# mikromedia_shield.net
KiCad netlist of a schematic drawn in EAGLE
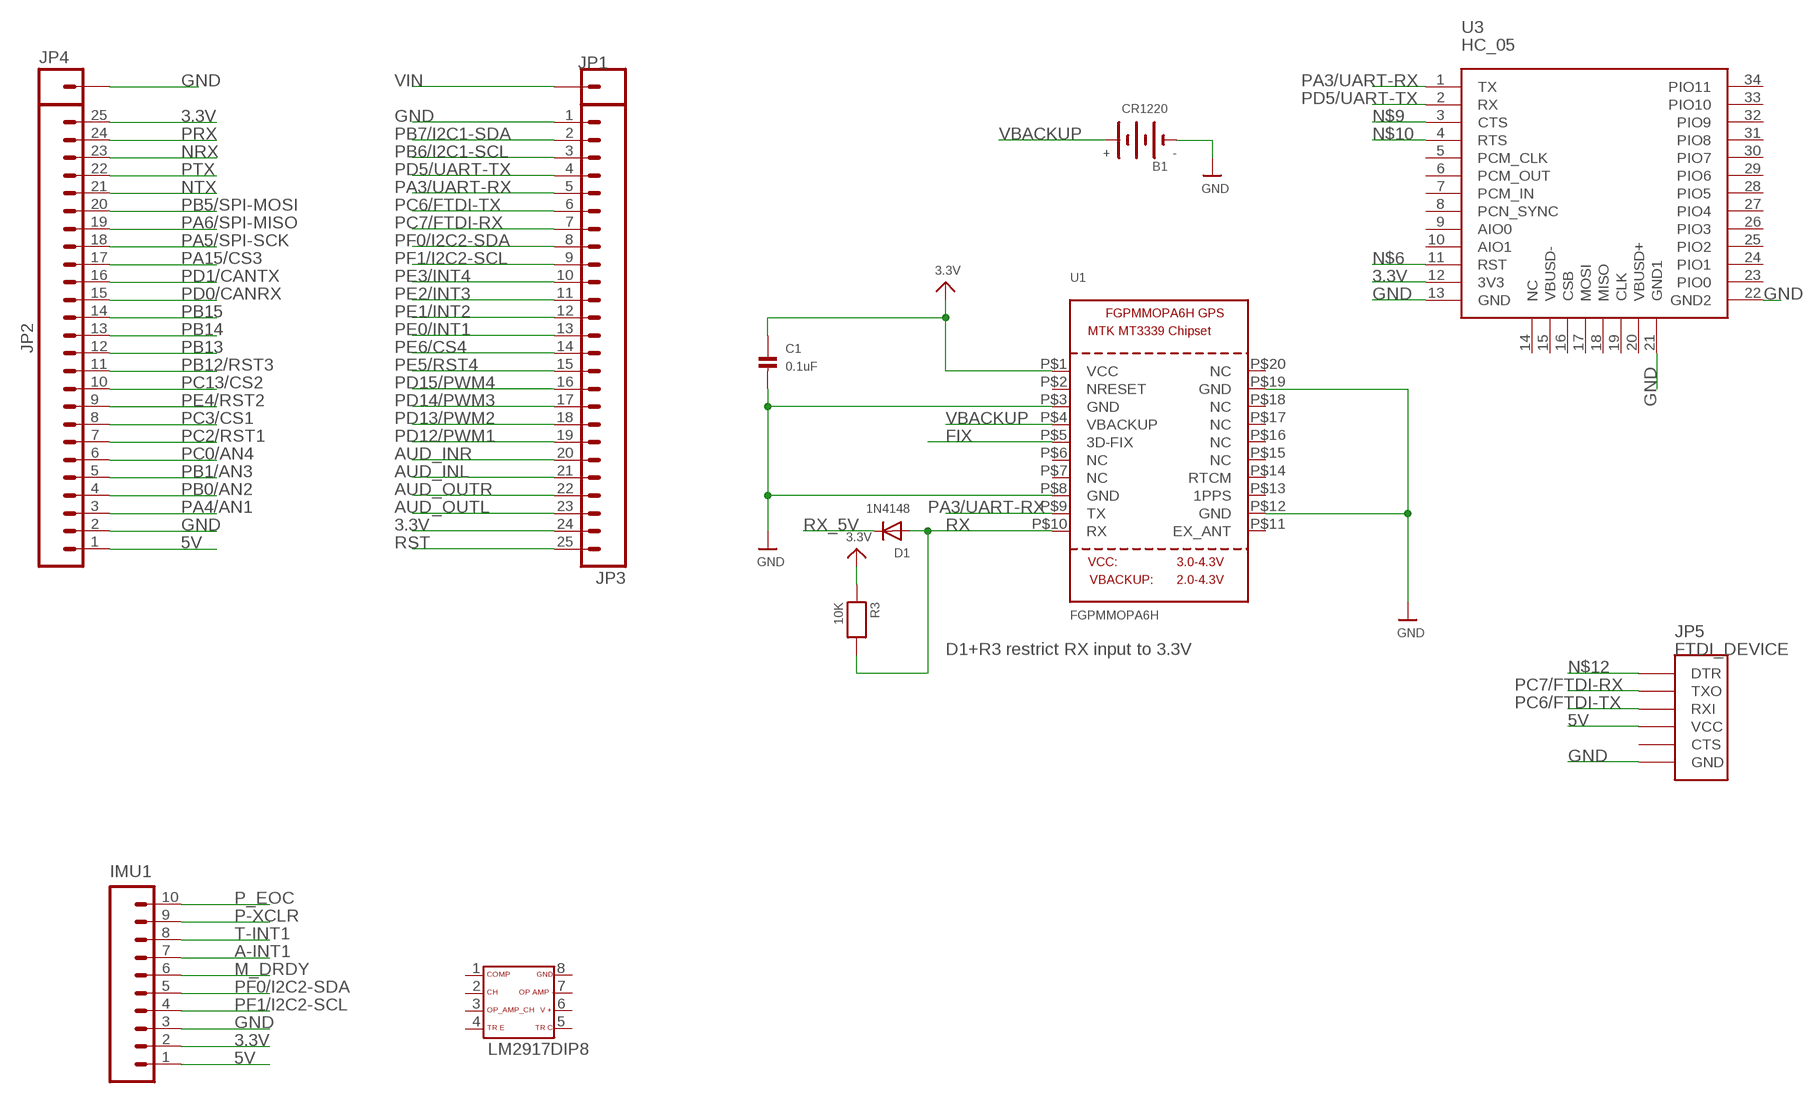
[diagram p0: schematic, sheet 1]

(export (version "E")
  (design (tool "Eeschema 10.0.6"))
  (components
    (comp (ref "B1")
      (value "CR1220")
      (footprint "eagle-import:CR1220")
      (libsource (lib "eagle-import") (part "BATTERYCR1220_SMT"))
    )
    (comp (ref "C1")
      (value "0.1uF")
      (footprint "eagle-import:0805")
      (libsource (lib "eagle-import") (part "CAP_CERAMIC0805"))
    )
    (comp (ref "D1")
      (value "1N4148")
      (footprint "eagle-import:SOD-323F")
      (libsource (lib "eagle-import") (part "DIODESOD-323F"))
    )
    (comp (ref "IC1")
      (value "LM2917DIP8")
      (footprint "eagle-import:LM2917_DIP8")
      (libsource (lib "eagle-import") (part "LM2917DIP8"))
    )
    (comp (ref "IMU1")
      (value "IMU")
      (footprint "eagle-import:1X10_LOCK_LONGPADS")
      (libsource (lib "eagle-import") (part "M10LOCK_LONGPADS"))
    )
    (comp (ref "JP1")
      (value "M01PTH")
      (footprint "eagle-import:1X01")
      (libsource (lib "eagle-import") (part "M01PTH"))
    )
    (comp (ref "JP2")
      (value "M25LOCK_LONGPADS")
      (footprint "eagle-import:1X25_LOCK_LONGPADS")
      (libsource (lib "eagle-import") (part "M25LOCK_LONGPADS"))
    )
    (comp (ref "JP3")
      (value "M25LOCK_LONGPADS")
      (footprint "eagle-import:1X25_LOCK_LONGPADS")
      (libsource (lib "eagle-import") (part "M25LOCK_LONGPADS"))
    )
    (comp (ref "JP4")
      (value "M01PTH")
      (footprint "eagle-import:1X01")
      (libsource (lib "eagle-import") (part "M01PTH"))
    )
    (comp (ref "JP5")
      (value "FTDI_DEVICE")
      (footprint "eagle-import:FTDI_DEVICE_SIDE")
      (libsource (lib "eagle-import") (part "FTDI_DEVICE"))
    )
    (comp (ref "R3")
      (value "10K")
      (footprint "eagle-import:0805")
      (libsource (lib "eagle-import") (part "RESISTOR0805"))
    )
    (comp (ref "U1")
      (value "FGPMMOPA6H")
      (footprint "eagle-import:FGPMMOPA6H")
      (libsource (lib "eagle-import") (part "GPS_FGPMMOPA6H"))
    )
    (comp (ref "U3")
      (value "HC_05")
      (footprint "eagle-import:BLUETOOTH_SMD")
      (libsource (lib "eagle-import") (part "HC_05"))
    )
  )
  (nets
    (net (code "1") (name "/5V") (class "Default")
      (node (ref "IMU1") (pin "1") (pinfunction "1_1") (pintype "passive"))
      (node (ref "JP2") (pin "1") (pinfunction "1_1") (pintype "passive"))
      (node (ref "JP5") (pin "P$4") (pinfunction "VCC_P$4") (pintype "bidirectional"))
    )
    (net (code "2") (name "/A-INT1") (class "Default")
      (node (ref "IMU1") (pin "7") (pinfunction "7_7") (pintype "passive"))
    )
    (net (code "3") (name "/AUD_INL") (class "Default")
      (node (ref "JP3") (pin "21") (pinfunction "21_21") (pintype "passive"))
    )
    (net (code "4") (name "/AUD_INR") (class "Default")
      (node (ref "JP3") (pin "20") (pinfunction "20_20") (pintype "passive"))
    )
    (net (code "5") (name "/AUD_OUTL") (class "Default")
      (node (ref "JP3") (pin "23") (pinfunction "23_23") (pintype "passive"))
    )
    (net (code "6") (name "/AUD_OUTR") (class "Default")
      (node (ref "JP3") (pin "22") (pinfunction "22_22") (pintype "passive"))
    )
    (net (code "7") (name "/FIX") (class "Default")
      (node (ref "U1") (pin "P$5") (pinfunction "3D-FIX_P$5") (pintype "bidirectional"))
    )
    (net (code "8") (name "/M_DRDY") (class "Default")
      (node (ref "IMU1") (pin "6") (pinfunction "6_6") (pintype "passive"))
    )
    (net (code "9") (name "/N$6") (class "Default")
      (node (ref "U3") (pin "11") (pinfunction "RST_11") (pintype "bidirectional"))
    )
    (net (code "10") (name "/N$9") (class "Default")
      (node (ref "U3") (pin "3") (pinfunction "CTS_3") (pintype "bidirectional"))
    )
    (net (code "11") (name "/N$10") (class "Default")
      (node (ref "U3") (pin "4") (pinfunction "RTS_4") (pintype "bidirectional"))
    )
    (net (code "12") (name "/N$12") (class "Default")
      (node (ref "JP5") (pin "P$1") (pinfunction "DTR_P$1") (pintype "bidirectional"))
    )
    (net (code "13") (name "/NRX") (class "Default")
      (node (ref "JP2") (pin "23") (pinfunction "23_23") (pintype "passive"))
    )
    (net (code "14") (name "/NTX") (class "Default")
      (node (ref "JP2") (pin "21") (pinfunction "21_21") (pintype "passive"))
    )
    (net (code "15") (name "/P-XCLR") (class "Default")
      (node (ref "IMU1") (pin "9") (pinfunction "9_9") (pintype "passive"))
    )
    (net (code "16") (name "/PA3{slash}UART-RX") (class "Default")
      (node (ref "JP3") (pin "5") (pinfunction "5_5") (pintype "passive"))
      (node (ref "U1") (pin "P$9") (pinfunction "TX_P$9") (pintype "bidirectional"))
      (node (ref "U3") (pin "1") (pinfunction "TX_1") (pintype "bidirectional"))
    )
    (net (code "17") (name "/PA4{slash}AN1") (class "Default")
      (node (ref "JP2") (pin "3") (pinfunction "3_3") (pintype "passive"))
    )
    (net (code "18") (name "/PA5{slash}SPI-SCK") (class "Default")
      (node (ref "JP2") (pin "18") (pinfunction "18_18") (pintype "passive"))
    )
    (net (code "19") (name "/PA6{slash}SPI-MISO") (class "Default")
      (node (ref "JP2") (pin "19") (pinfunction "19_19") (pintype "passive"))
    )
    (net (code "20") (name "/PA15{slash}CS3") (class "Default")
      (node (ref "JP2") (pin "17") (pinfunction "17_17") (pintype "passive"))
    )
    (net (code "21") (name "/PB0{slash}AN2") (class "Default")
      (node (ref "JP2") (pin "4") (pinfunction "4_4") (pintype "passive"))
    )
    (net (code "22") (name "/PB1{slash}AN3") (class "Default")
      (node (ref "JP2") (pin "5") (pinfunction "5_5") (pintype "passive"))
    )
    (net (code "23") (name "/PB5{slash}SPI-MOSI") (class "Default")
      (node (ref "JP2") (pin "20") (pinfunction "20_20") (pintype "passive"))
    )
    (net (code "24") (name "/PB6{slash}I2C1-SCL") (class "Default")
      (node (ref "JP3") (pin "3") (pinfunction "3_3") (pintype "passive"))
    )
    (net (code "25") (name "/PB7{slash}I2C1-SDA") (class "Default")
      (node (ref "JP3") (pin "2") (pinfunction "2_2") (pintype "passive"))
    )
    (net (code "26") (name "/PB12{slash}RST3") (class "Default")
      (node (ref "JP2") (pin "11") (pinfunction "11_11") (pintype "passive"))
    )
    (net (code "27") (name "/PB13") (class "Default")
      (node (ref "JP2") (pin "12") (pinfunction "12_12") (pintype "passive"))
    )
    (net (code "28") (name "/PB14") (class "Default")
      (node (ref "JP2") (pin "13") (pinfunction "13_13") (pintype "passive"))
    )
    (net (code "29") (name "/PB15") (class "Default")
      (node (ref "JP2") (pin "14") (pinfunction "14_14") (pintype "passive"))
    )
    (net (code "30") (name "/PC0{slash}AN4") (class "Default")
      (node (ref "JP2") (pin "6") (pinfunction "6_6") (pintype "passive"))
    )
    (net (code "31") (name "/PC2{slash}RST1") (class "Default")
      (node (ref "JP2") (pin "7") (pinfunction "7_7") (pintype "passive"))
    )
    (net (code "32") (name "/PC3{slash}CS1") (class "Default")
      (node (ref "JP2") (pin "8") (pinfunction "8_8") (pintype "passive"))
    )
    (net (code "33") (name "/PC6{slash}FTDI-TX") (class "Default")
      (node (ref "JP3") (pin "6") (pinfunction "6_6") (pintype "passive"))
      (node (ref "JP5") (pin "P$3") (pinfunction "RXI_P$3") (pintype "bidirectional"))
    )
    (net (code "34") (name "/PC7{slash}FTDI-RX") (class "Default")
      (node (ref "JP3") (pin "7") (pinfunction "7_7") (pintype "passive"))
      (node (ref "JP5") (pin "P$2") (pinfunction "TXO_P$2") (pintype "bidirectional"))
    )
    (net (code "35") (name "/PC13{slash}CS2") (class "Default")
      (node (ref "JP2") (pin "10") (pinfunction "10_10") (pintype "passive"))
    )
    (net (code "36") (name "/PD0{slash}CANRX") (class "Default")
      (node (ref "JP2") (pin "15") (pinfunction "15_15") (pintype "passive"))
    )
    (net (code "37") (name "/PD1{slash}CANTX") (class "Default")
      (node (ref "JP2") (pin "16") (pinfunction "16_16") (pintype "passive"))
    )
    (net (code "38") (name "/PD5{slash}UART-TX") (class "Default")
      (node (ref "JP3") (pin "4") (pinfunction "4_4") (pintype "passive"))
      (node (ref "U3") (pin "2") (pinfunction "RX_2") (pintype "bidirectional"))
    )
    (net (code "39") (name "/PD12{slash}PWM1") (class "Default")
      (node (ref "JP3") (pin "19") (pinfunction "19_19") (pintype "passive"))
    )
    (net (code "40") (name "/PD13{slash}PWM2") (class "Default")
      (node (ref "JP3") (pin "18") (pinfunction "18_18") (pintype "passive"))
    )
    (net (code "41") (name "/PD14{slash}PWM3") (class "Default")
      (node (ref "JP3") (pin "17") (pinfunction "17_17") (pintype "passive"))
    )
    (net (code "42") (name "/PD15{slash}PWM4") (class "Default")
      (node (ref "JP3") (pin "16") (pinfunction "16_16") (pintype "passive"))
    )
    (net (code "43") (name "/PE0{slash}INT1") (class "Default")
      (node (ref "JP3") (pin "13") (pinfunction "13_13") (pintype "passive"))
    )
    (net (code "44") (name "/PE1{slash}INT2") (class "Default")
      (node (ref "JP3") (pin "12") (pinfunction "12_12") (pintype "passive"))
    )
    (net (code "45") (name "/PE2{slash}INT3") (class "Default")
      (node (ref "JP3") (pin "11") (pinfunction "11_11") (pintype "passive"))
    )
    (net (code "46") (name "/PE3{slash}INT4") (class "Default")
      (node (ref "JP3") (pin "10") (pinfunction "10_10") (pintype "passive"))
    )
    (net (code "47") (name "/PE4{slash}RST2") (class "Default")
      (node (ref "JP2") (pin "9") (pinfunction "9_9") (pintype "passive"))
    )
    (net (code "48") (name "/PE5{slash}RST4") (class "Default")
      (node (ref "JP3") (pin "15") (pinfunction "15_15") (pintype "passive"))
    )
    (net (code "49") (name "/PE6{slash}CS4") (class "Default")
      (node (ref "JP3") (pin "14") (pinfunction "14_14") (pintype "passive"))
    )
    (net (code "50") (name "/PF0{slash}I2C2-SDA") (class "Default")
      (node (ref "IMU1") (pin "5") (pinfunction "5_5") (pintype "passive"))
      (node (ref "JP3") (pin "8") (pinfunction "8_8") (pintype "passive"))
    )
    (net (code "51") (name "/PF1{slash}I2C2-SCL") (class "Default")
      (node (ref "IMU1") (pin "4") (pinfunction "4_4") (pintype "passive"))
      (node (ref "JP3") (pin "9") (pinfunction "9_9") (pintype "passive"))
    )
    (net (code "52") (name "/PRX") (class "Default")
      (node (ref "JP2") (pin "24") (pinfunction "24_24") (pintype "passive"))
    )
    (net (code "53") (name "/PTX") (class "Default")
      (node (ref "JP2") (pin "22") (pinfunction "22_22") (pintype "passive"))
    )
    (net (code "54") (name "/P_EOC") (class "Default")
      (node (ref "IMU1") (pin "10") (pinfunction "10_10") (pintype "passive"))
    )
    (net (code "55") (name "/RST") (class "Default")
      (node (ref "JP3") (pin "25") (pinfunction "25_25") (pintype "passive"))
    )
    (net (code "56") (name "/RX") (class "Default")
      (node (ref "D1") (pin "A") (pinfunction "A_A") (pintype "passive"))
      (node (ref "R3") (pin "2") (pinfunction "2_2") (pintype "passive"))
      (node (ref "U1") (pin "P$10") (pinfunction "RX_P$10") (pintype "bidirectional"))
    )
    (net (code "57") (name "/RX_5V") (class "Default")
      (node (ref "D1") (pin "C") (pinfunction "C_C") (pintype "passive"))
    )
    (net (code "58") (name "/T-INT1") (class "Default")
      (node (ref "IMU1") (pin "8") (pinfunction "8_8") (pintype "passive"))
    )
    (net (code "59") (name "/VBACKUP") (class "Default")
      (node (ref "B1") (pin "+$1") (pinfunction "+_+$1") (pintype "passive"))
      (node (ref "U1") (pin "P$4") (pinfunction "VBACKUP_P$4") (pintype "bidirectional"))
    )
    (net (code "60") (name "/VIN") (class "Default")
      (node (ref "JP1") (pin "1") (pinfunction "1_1") (pintype "passive"))
    )
    (net (code "61") (name "3.3V") (class "Default")
      (node (ref "C1") (pin "1") (pinfunction "P$1_1") (pintype "passive"))
      (node (ref "IMU1") (pin "2") (pinfunction "2_2") (pintype "passive"))
      (node (ref "JP2") (pin "25") (pinfunction "25_25") (pintype "passive"))
      (node (ref "JP3") (pin "24") (pinfunction "24_24") (pintype "passive"))
      (node (ref "R3") (pin "1") (pinfunction "1_1") (pintype "passive"))
      (node (ref "U1") (pin "P$1") (pinfunction "VCC_P$1") (pintype "bidirectional"))
      (node (ref "U3") (pin "12") (pinfunction "3V3_12") (pintype "bidirectional"))
    )
    (net (code "62") (name "GND") (class "Default")
      (node (ref "B1") (pin "-") (pinfunction "-_-") (pintype "passive"))
      (node (ref "C1") (pin "2") (pinfunction "P$2_2") (pintype "passive"))
      (node (ref "IMU1") (pin "3") (pinfunction "3_3") (pintype "passive"))
      (node (ref "JP2") (pin "2") (pinfunction "2_2") (pintype "passive"))
      (node (ref "JP3") (pin "1") (pinfunction "1_1") (pintype "passive"))
      (node (ref "JP4") (pin "1") (pinfunction "1_1") (pintype "passive"))
      (node (ref "JP5") (pin "P$6") (pinfunction "GND_P$6") (pintype "bidirectional"))
      (node (ref "U1") (pin "P$12") (pinfunction "GND_P$12") (pintype "bidirectional"))
      (node (ref "U1") (pin "P$19") (pinfunction "GND_P$19") (pintype "bidirectional"))
      (node (ref "U1") (pin "P$3") (pinfunction "GND_P$3") (pintype "bidirectional"))
      (node (ref "U1") (pin "P$8") (pinfunction "GND_P$8") (pintype "bidirectional"))
      (node (ref "U3") (pin "13") (pinfunction "GND_13") (pintype "bidirectional"))
      (node (ref "U3") (pin "21") (pinfunction "GND1_21") (pintype "bidirectional"))
      (node (ref "U3") (pin "22") (pinfunction "GND2_22") (pintype "bidirectional"))
    )
    (net (code "63") (name "unconnected-(IC1-Pad1)") (class "Default")
      (node (ref "IC1") (pin "1") (pinfunction "1_1") (pintype "passive"))
    )
    (net (code "64") (name "unconnected-(IC1-Pad2)") (class "Default")
      (node (ref "IC1") (pin "2") (pinfunction "2_2") (pintype "passive"))
    )
    (net (code "65") (name "unconnected-(IC1-Pad3)") (class "Default")
      (node (ref "IC1") (pin "3") (pinfunction "3_3") (pintype "passive"))
    )
    (net (code "66") (name "unconnected-(IC1-Pad4)") (class "Default")
      (node (ref "IC1") (pin "4") (pinfunction "4_4") (pintype "passive"))
    )
    (net (code "67") (name "unconnected-(IC1-Pad5)") (class "Default")
      (node (ref "IC1") (pin "5") (pinfunction "5_5") (pintype "passive"))
    )
    (net (code "68") (name "unconnected-(IC1-Pad6)") (class "Default")
      (node (ref "IC1") (pin "6") (pinfunction "6_6") (pintype "passive"))
    )
    (net (code "69") (name "unconnected-(IC1-Pad7)") (class "Default")
      (node (ref "IC1") (pin "7") (pinfunction "7_7") (pintype "passive"))
    )
    (net (code "70") (name "unconnected-(IC1-Pad8)") (class "Default")
      (node (ref "IC1") (pin "8") (pinfunction "8_8") (pintype "passive"))
    )
    (net (code "71") (name "unconnected-(JP5-CTS-PadP$5)") (class "Default")
      (node (ref "JP5") (pin "P$5") (pinfunction "CTS_P$5") (pintype "bidirectional"))
    )
    (net (code "72") (name "unconnected-(U1-1PPS-PadP$13)") (class "Default")
      (node (ref "U1") (pin "P$13") (pinfunction "1PPS_P$13") (pintype "bidirectional"))
    )
    (net (code "73") (name "unconnected-(U1-EX_ANT-PadP$11)") (class "Default")
      (node (ref "U1") (pin "P$11") (pinfunction "EX_ANT_P$11") (pintype "bidirectional"))
    )
    (net (code "74") (name "unconnected-(U1-NC-PadP$6)") (class "Default")
      (node (ref "U1") (pin "P$6") (pinfunction "NC_P$6") (pintype "bidirectional"))
    )
    (net (code "75") (name "unconnected-(U1-NC-PadP$7)") (class "Default")
      (node (ref "U1") (pin "P$7") (pinfunction "NC_P$7") (pintype "bidirectional"))
    )
    (net (code "76") (name "unconnected-(U1-NC-PadP$15)") (class "Default")
      (node (ref "U1") (pin "P$15") (pinfunction "NC_P$15") (pintype "bidirectional"))
    )
    (net (code "77") (name "unconnected-(U1-NC-PadP$16)") (class "Default")
      (node (ref "U1") (pin "P$16") (pinfunction "NC_P$16") (pintype "bidirectional"))
    )
    (net (code "78") (name "unconnected-(U1-NC-PadP$17)") (class "Default")
      (node (ref "U1") (pin "P$17") (pinfunction "NC_P$17") (pintype "bidirectional"))
    )
    (net (code "79") (name "unconnected-(U1-NC-PadP$18)") (class "Default")
      (node (ref "U1") (pin "P$18") (pinfunction "NC_P$18") (pintype "bidirectional"))
    )
    (net (code "80") (name "unconnected-(U1-NC-PadP$20)") (class "Default")
      (node (ref "U1") (pin "P$20") (pinfunction "NC_P$20") (pintype "bidirectional"))
    )
    (net (code "81") (name "unconnected-(U1-NRESET-PadP$2)") (class "Default")
      (node (ref "U1") (pin "P$2") (pinfunction "NRESET_P$2") (pintype "bidirectional"))
    )
    (net (code "82") (name "unconnected-(U1-RTCM-PadP$14)") (class "Default")
      (node (ref "U1") (pin "P$14") (pinfunction "RTCM_P$14") (pintype "bidirectional"))
    )
    (net (code "83") (name "unconnected-(U3-AIO0-Pad9)") (class "Default")
      (node (ref "U3") (pin "9") (pinfunction "AIO0_9") (pintype "bidirectional"))
    )
    (net (code "84") (name "unconnected-(U3-AIO1-Pad10)") (class "Default")
      (node (ref "U3") (pin "10") (pinfunction "AIO1_10") (pintype "bidirectional"))
    )
    (net (code "85") (name "unconnected-(U3-CLK-Pad19)") (class "Default")
      (node (ref "U3") (pin "19") (pinfunction "CLK_19") (pintype "bidirectional"))
    )
    (net (code "86") (name "unconnected-(U3-CSB-Pad16)") (class "Default")
      (node (ref "U3") (pin "16") (pinfunction "CSB_16") (pintype "bidirectional"))
    )
    (net (code "87") (name "unconnected-(U3-MISO-Pad18)") (class "Default")
      (node (ref "U3") (pin "18") (pinfunction "MISO_18") (pintype "bidirectional"))
    )
    (net (code "88") (name "unconnected-(U3-MOSI-Pad17)") (class "Default")
      (node (ref "U3") (pin "17") (pinfunction "MOSI_17") (pintype "bidirectional"))
    )
    (net (code "89") (name "unconnected-(U3-NC-Pad14)") (class "Default")
      (node (ref "U3") (pin "14") (pinfunction "NC_14") (pintype "bidirectional"))
    )
    (net (code "90") (name "unconnected-(U3-PCM_CLK-Pad5)") (class "Default")
      (node (ref "U3") (pin "5") (pinfunction "PCM_CLK_5") (pintype "bidirectional"))
    )
    (net (code "91") (name "unconnected-(U3-PCM_IN-Pad7)") (class "Default")
      (node (ref "U3") (pin "7") (pinfunction "PCM_IN_7") (pintype "bidirectional"))
    )
    (net (code "92") (name "unconnected-(U3-PCM_OUT-Pad6)") (class "Default")
      (node (ref "U3") (pin "6") (pinfunction "PCM_OUT_6") (pintype "bidirectional"))
    )
    (net (code "93") (name "unconnected-(U3-PCN_SYNC-Pad8)") (class "Default")
      (node (ref "U3") (pin "8") (pinfunction "PCN_SYNC_8") (pintype "bidirectional"))
    )
    (net (code "94") (name "unconnected-(U3-PIO0-Pad23)") (class "Default")
      (node (ref "U3") (pin "23") (pinfunction "PIO0_23") (pintype "bidirectional"))
    )
    (net (code "95") (name "unconnected-(U3-PIO1-Pad24)") (class "Default")
      (node (ref "U3") (pin "24") (pinfunction "PIO1_24") (pintype "bidirectional"))
    )
    (net (code "96") (name "unconnected-(U3-PIO2-Pad25)") (class "Default")
      (node (ref "U3") (pin "25") (pinfunction "PIO2_25") (pintype "bidirectional"))
    )
    (net (code "97") (name "unconnected-(U3-PIO3-Pad26)") (class "Default")
      (node (ref "U3") (pin "26") (pinfunction "PIO3_26") (pintype "bidirectional"))
    )
    (net (code "98") (name "unconnected-(U3-PIO4-Pad27)") (class "Default")
      (node (ref "U3") (pin "27") (pinfunction "PIO4_27") (pintype "bidirectional"))
    )
    (net (code "99") (name "unconnected-(U3-PIO5-Pad28)") (class "Default")
      (node (ref "U3") (pin "28") (pinfunction "PIO5_28") (pintype "bidirectional"))
    )
    (net (code "100") (name "unconnected-(U3-PIO6-Pad29)") (class "Default")
      (node (ref "U3") (pin "29") (pinfunction "PIO6_29") (pintype "bidirectional"))
    )
    (net (code "101") (name "unconnected-(U3-PIO7-Pad30)") (class "Default")
      (node (ref "U3") (pin "30") (pinfunction "PIO7_30") (pintype "bidirectional"))
    )
    (net (code "102") (name "unconnected-(U3-PIO8-Pad31)") (class "Default")
      (node (ref "U3") (pin "31") (pinfunction "PIO8_31") (pintype "bidirectional"))
    )
    (net (code "103") (name "unconnected-(U3-PIO9-Pad32)") (class "Default")
      (node (ref "U3") (pin "32") (pinfunction "PIO9_32") (pintype "bidirectional"))
    )
    (net (code "104") (name "unconnected-(U3-PIO10-Pad33)") (class "Default")
      (node (ref "U3") (pin "33") (pinfunction "PIO10_33") (pintype "bidirectional"))
    )
    (net (code "105") (name "unconnected-(U3-PIO11-Pad34)") (class "Default")
      (node (ref "U3") (pin "34") (pinfunction "PIO11_34") (pintype "bidirectional"))
    )
    (net (code "106") (name "unconnected-(U3-VBUSD+-Pad20)") (class "Default")
      (node (ref "U3") (pin "20") (pinfunction "VBUSD+_20") (pintype "bidirectional"))
    )
    (net (code "107") (name "unconnected-(U3-VBUSD--Pad15)") (class "Default")
      (node (ref "U3") (pin "15") (pinfunction "VBUSD-_15") (pintype "bidirectional"))
    )
  )
)
